# aquafrownie.net
KiCad netlist of a schematic drawn in EAGLE
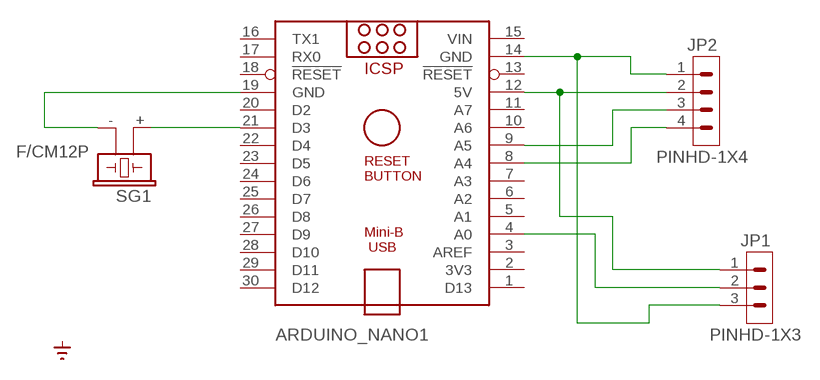
[diagram p0: schematic, sheet 1]

(export (version "E")
  (design (tool "Eeschema 10.0.6"))
  (components
    (comp (ref "ARDUINO_NANO1")
      (value "ARDUINO_NANO")
      (footprint "eagle-import:ARDUINO_NANO")
      (libsource (lib "eagle-import") (part "ARDUINO_NANO"))
    )
    (comp (ref "JP1")
      (value "PINHD-1X3")
      (footprint "eagle-import:1X03")
      (libsource (lib "eagle-import") (part "PINHD-1X3"))
    )
    (comp (ref "JP2")
      (value "PINHD-1X4")
      (footprint "eagle-import:1X04")
      (libsource (lib "eagle-import") (part "PINHD-1X4"))
    )
    (comp (ref "SG1")
      (value "F/CM12P")
      (footprint "eagle-import:F_CM12P")
      (libsource (lib "eagle-import") (part "F/CM12P"))
    )
  )
  (nets
    (net (code "1") (name "/VIN") (class "Default")
      (node (ref "ARDUINO_NANO1") (pin "15") (pinfunction "VIN_15") (pintype "power_in"))
    )
    (net (code "2") (name "Net-(ARDUINO_NANO1-5V)") (class "Default")
      (node (ref "ARDUINO_NANO1") (pin "12") (pinfunction "5V_12") (pintype "power_in"))
      (node (ref "JP1") (pin "1") (pinfunction "1_1") (pintype "passive"))
      (node (ref "JP2") (pin "2") (pinfunction "2_2") (pintype "passive"))
    )
    (net (code "3") (name "Net-(ARDUINO_NANO1-A0)") (class "Default")
      (node (ref "ARDUINO_NANO1") (pin "4") (pinfunction "A0_4") (pintype "bidirectional"))
      (node (ref "JP1") (pin "2") (pinfunction "2_2") (pintype "passive"))
    )
    (net (code "4") (name "Net-(ARDUINO_NANO1-A4)") (class "Default")
      (node (ref "ARDUINO_NANO1") (pin "8") (pinfunction "A4_8") (pintype "bidirectional"))
      (node (ref "JP2") (pin "4") (pinfunction "4_4") (pintype "passive"))
    )
    (net (code "5") (name "Net-(ARDUINO_NANO1-A5)") (class "Default")
      (node (ref "ARDUINO_NANO1") (pin "9") (pinfunction "A5_9") (pintype "bidirectional"))
      (node (ref "JP2") (pin "3") (pinfunction "3_3") (pintype "passive"))
    )
    (net (code "6") (name "Net-(ARDUINO_NANO1-D3)") (class "Default")
      (node (ref "ARDUINO_NANO1") (pin "21") (pinfunction "D3_21") (pintype "bidirectional"))
      (node (ref "SG1") (pin "+") (pinfunction "1_+") (pintype "passive"))
    )
    (net (code "7") (name "Net-(ARDUINO_NANO1-GND-Pad14)") (class "Default")
      (node (ref "ARDUINO_NANO1") (pin "14") (pinfunction "GND_14") (pintype "power_in"))
      (node (ref "JP1") (pin "3") (pinfunction "3_3") (pintype "passive"))
      (node (ref "JP2") (pin "1") (pinfunction "1_1") (pintype "passive"))
    )
    (net (code "8") (name "Net-(SG1-2)") (class "Default")
      (node (ref "ARDUINO_NANO1") (pin "19") (pinfunction "GND_19") (pintype "power_in"))
      (node (ref "SG1") (pin "-") (pinfunction "2_-") (pintype "passive"))
    )
    (net (code "10") (name "unconnected-(ARDUINO_NANO1-3V3-Pad2)") (class "Default")
      (node (ref "ARDUINO_NANO1") (pin "2") (pinfunction "3V3_2") (pintype "output"))
    )
    (net (code "11") (name "unconnected-(ARDUINO_NANO1-A1-Pad5)") (class "Default")
      (node (ref "ARDUINO_NANO1") (pin "5") (pinfunction "A1_5") (pintype "bidirectional"))
    )
    (net (code "12") (name "unconnected-(ARDUINO_NANO1-A2-Pad6)") (class "Default")
      (node (ref "ARDUINO_NANO1") (pin "6") (pinfunction "A2_6") (pintype "bidirectional"))
    )
    (net (code "13") (name "unconnected-(ARDUINO_NANO1-A3-Pad7)") (class "Default")
      (node (ref "ARDUINO_NANO1") (pin "7") (pinfunction "A3_7") (pintype "bidirectional"))
    )
    (net (code "14") (name "unconnected-(ARDUINO_NANO1-A6-Pad10)") (class "Default")
      (node (ref "ARDUINO_NANO1") (pin "10") (pinfunction "A6_10") (pintype "bidirectional"))
    )
    (net (code "15") (name "unconnected-(ARDUINO_NANO1-A7-Pad11)") (class "Default")
      (node (ref "ARDUINO_NANO1") (pin "11") (pinfunction "A7_11") (pintype "bidirectional"))
    )
    (net (code "16") (name "unconnected-(ARDUINO_NANO1-AREF-Pad3)") (class "Default")
      (node (ref "ARDUINO_NANO1") (pin "3") (pinfunction "AREF_3") (pintype "input"))
    )
    (net (code "17") (name "unconnected-(ARDUINO_NANO1-D2-Pad20)") (class "Default")
      (node (ref "ARDUINO_NANO1") (pin "20") (pinfunction "D2_20") (pintype "bidirectional"))
    )
    (net (code "18") (name "unconnected-(ARDUINO_NANO1-D4-Pad22)") (class "Default")
      (node (ref "ARDUINO_NANO1") (pin "22") (pinfunction "D4_22") (pintype "bidirectional"))
    )
    (net (code "19") (name "unconnected-(ARDUINO_NANO1-D5-Pad23)") (class "Default")
      (node (ref "ARDUINO_NANO1") (pin "23") (pinfunction "D5_23") (pintype "bidirectional"))
    )
    (net (code "20") (name "unconnected-(ARDUINO_NANO1-D6-Pad24)") (class "Default")
      (node (ref "ARDUINO_NANO1") (pin "24") (pinfunction "D6_24") (pintype "bidirectional"))
    )
    (net (code "21") (name "unconnected-(ARDUINO_NANO1-D7-Pad25)") (class "Default")
      (node (ref "ARDUINO_NANO1") (pin "25") (pinfunction "D7_25") (pintype "bidirectional"))
    )
    (net (code "22") (name "unconnected-(ARDUINO_NANO1-D8-Pad26)") (class "Default")
      (node (ref "ARDUINO_NANO1") (pin "26") (pinfunction "D8_26") (pintype "bidirectional"))
    )
    (net (code "23") (name "unconnected-(ARDUINO_NANO1-D9-Pad27)") (class "Default")
      (node (ref "ARDUINO_NANO1") (pin "27") (pinfunction "D9_27") (pintype "bidirectional"))
    )
    (net (code "24") (name "unconnected-(ARDUINO_NANO1-D10-Pad28)") (class "Default")
      (node (ref "ARDUINO_NANO1") (pin "28") (pinfunction "D10_28") (pintype "bidirectional"))
    )
    (net (code "25") (name "unconnected-(ARDUINO_NANO1-D11-Pad29)") (class "Default")
      (node (ref "ARDUINO_NANO1") (pin "29") (pinfunction "D11_29") (pintype "bidirectional"))
    )
    (net (code "26") (name "unconnected-(ARDUINO_NANO1-D12-Pad30)") (class "Default")
      (node (ref "ARDUINO_NANO1") (pin "30") (pinfunction "D12_30") (pintype "bidirectional"))
    )
    (net (code "27") (name "unconnected-(ARDUINO_NANO1-D13-Pad1)") (class "Default")
      (node (ref "ARDUINO_NANO1") (pin "1") (pinfunction "D13_1") (pintype "bidirectional"))
    )
    (net (code "28") (name "unconnected-(ARDUINO_NANO1-RX0-Pad17)") (class "Default")
      (node (ref "ARDUINO_NANO1") (pin "17") (pinfunction "RX0_17") (pintype "bidirectional"))
    )
    (net (code "29") (name "unconnected-(ARDUINO_NANO1-TX1-Pad16)") (class "Default")
      (node (ref "ARDUINO_NANO1") (pin "16") (pinfunction "TX1_16") (pintype "bidirectional"))
    )
    (net (code "30") (name "unconnected-(ARDUINO_NANO1-~{RESET}-Pad13)") (class "Default")
      (node (ref "ARDUINO_NANO1") (pin "13") (pinfunction "~{RESET}_13") (pintype "input"))
    )
    (net (code "31") (name "unconnected-(ARDUINO_NANO1-~{RESET}-Pad18)") (class "Default")
      (node (ref "ARDUINO_NANO1") (pin "18") (pinfunction "~{RESET}_18") (pintype "input"))
    )
  )
)
